# QUDONG.net
KiCad netlist of a schematic drawn in Altium Designer
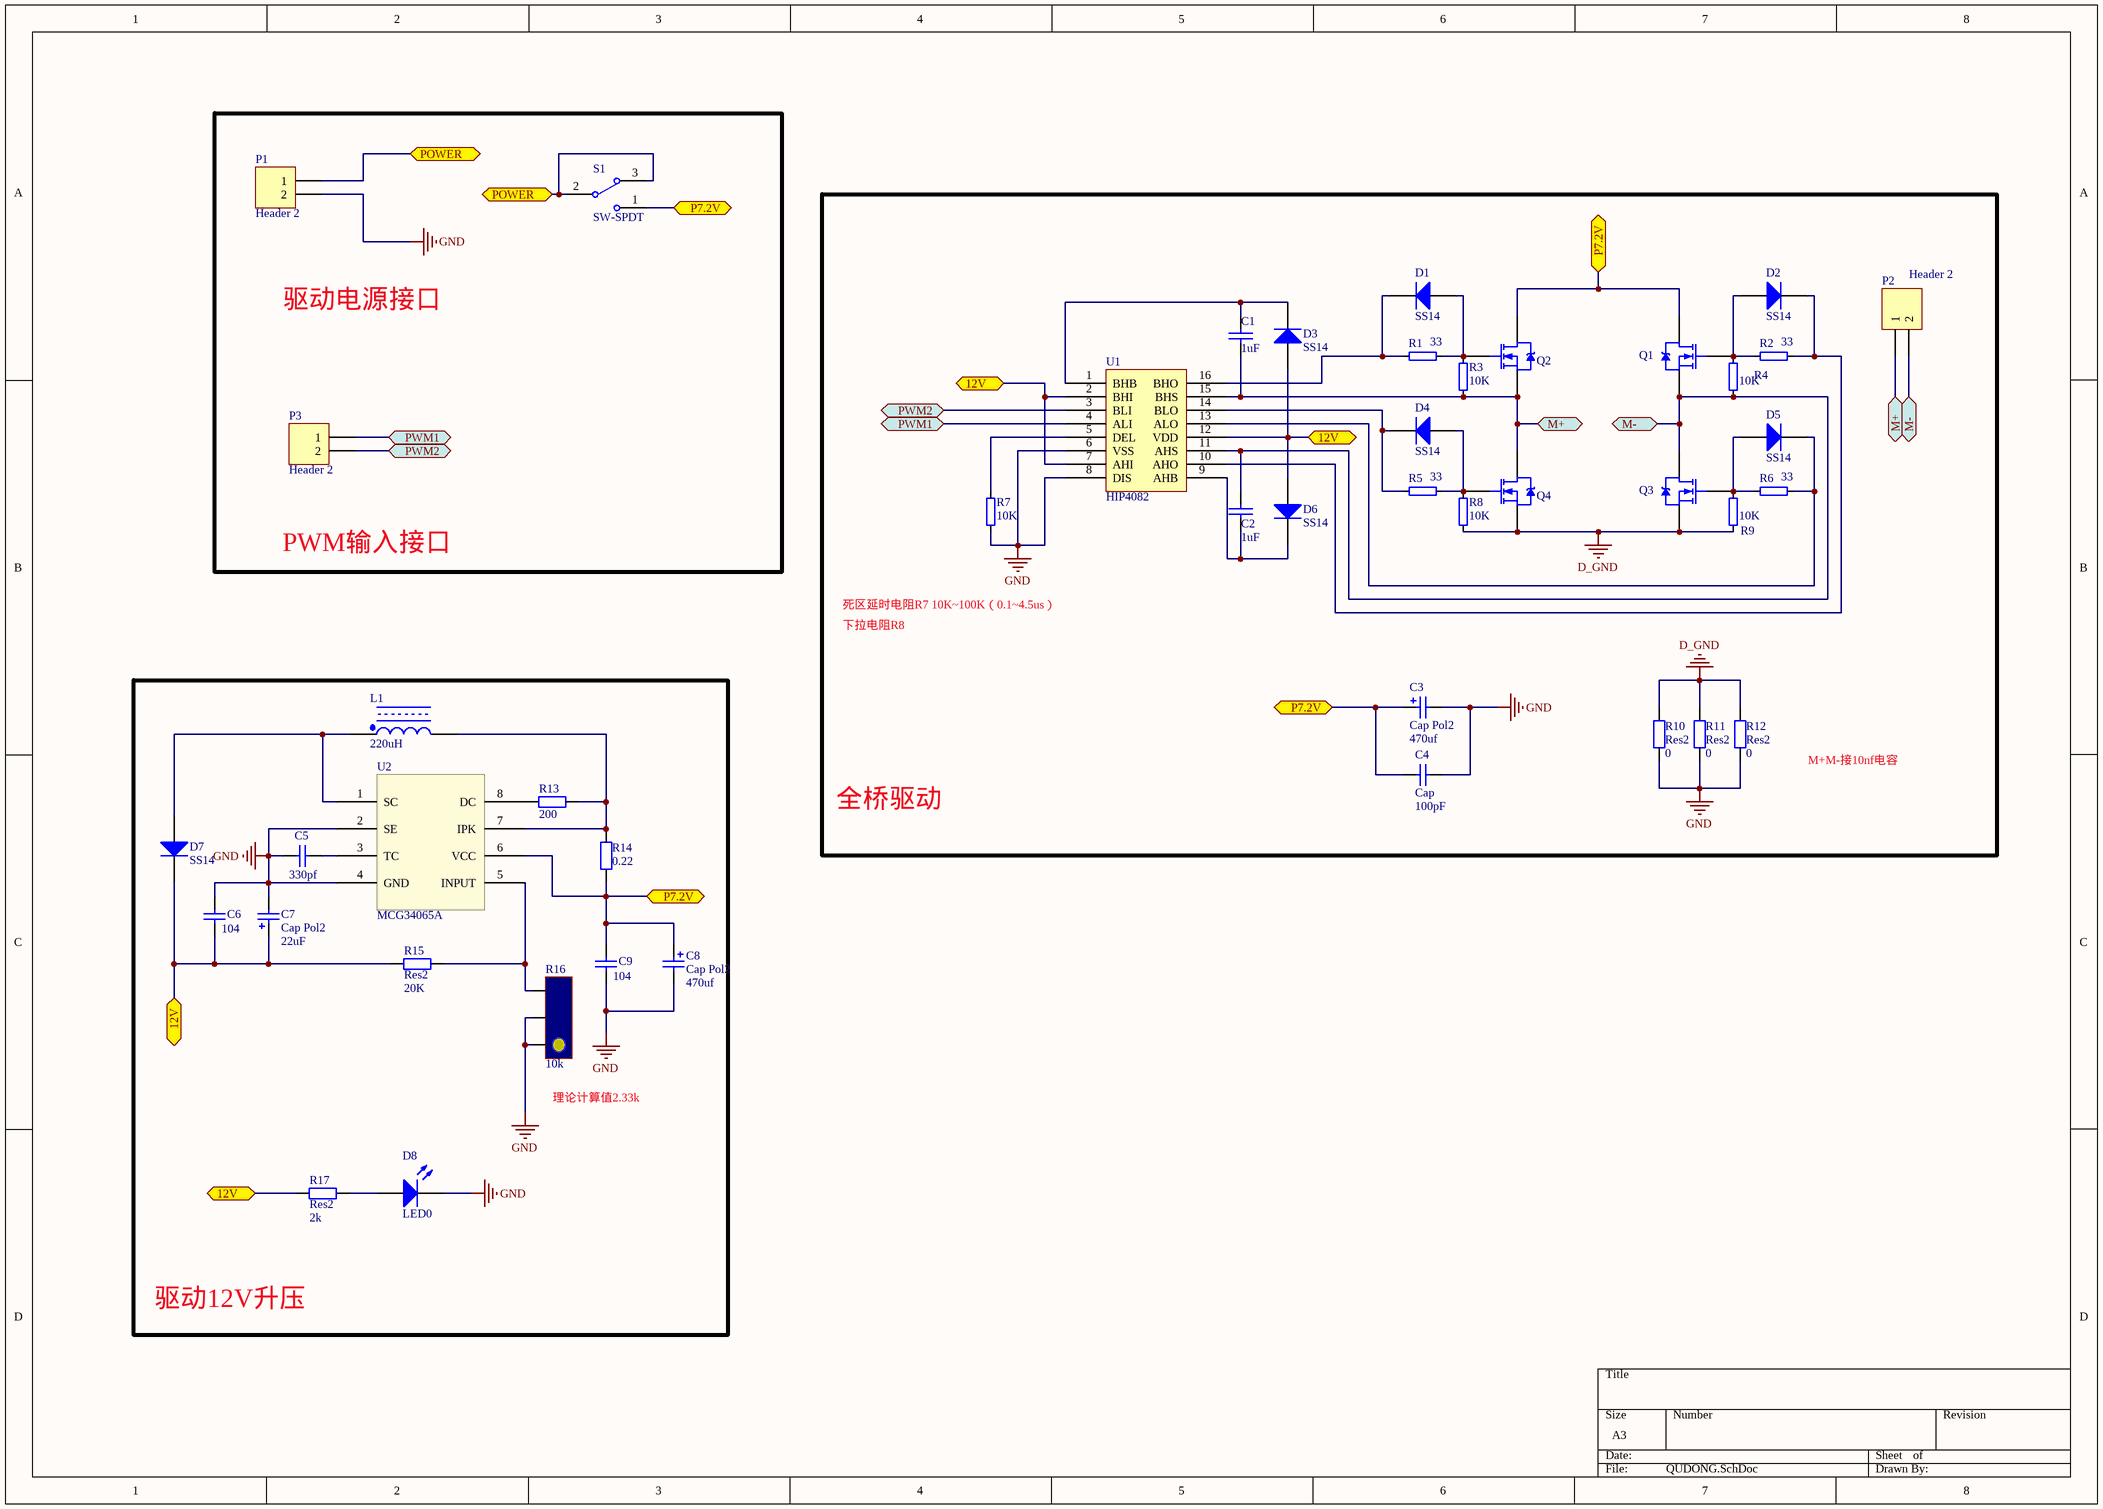
[diagram p0: QUDONG.SchDoc]

(export (version "E")
  (design (tool "Eeschema 10.0.6"))
  (components
    (comp (ref "C1")
      (value "1uF")
      (footprint "C-0805")
      (description "Capacitor")
      (libsource (lib "ZQ元件库") (part "CAP"))
    )
    (comp (ref "C2")
      (value "1uF")
      (footprint "C-0805")
      (description "Capacitor")
      (libsource (lib "ZQ元件库") (part "CAP"))
    )
    (comp (ref "C3")
      (value "Cap Pol2")
      (footprint "CAP-E1")
      (description "Polarized Capacitor (Axial)")
      (fields (field (name "ALTIUM_VALUE") "470uf") (field (name "PUBLISHER") "Altium Limited"))
      (libsource (lib "Miscellaneous Devices") (part "Cap Pol2"))
    )
    (comp (ref "C4")
      (value "Cap")
      (footprint "C-0805")
      (description "Capacitor")
      (fields (field (name "ALTIUM_VALUE") "100pF") (field (name "PUBLISHER") "Altium Limited"))
      (libsource (lib "Miscellaneous Devices") (part "Cap"))
    )
    (comp (ref "C5")
      (value "330pf")
      (footprint "C-0805")
      (description "Capacitor")
      (fields (field (name "Comment") "Cap") (field (name "PUBLISHER") "Altium Limited"))
      (libsource (lib "Miscellaneous Devices") (part "Cap"))
    )
    (comp (ref "C6")
      (value "104")
      (footprint "C-0805")
      (description "Capacitor")
      (fields (field (name "Comment") "Cap") (field (name "PUBLISHER") "Altium Limited"))
      (libsource (lib "Miscellaneous Devices") (part "Cap"))
    )
    (comp (ref "C7")
      (value "Cap Pol2")
      (footprint "1206")
      (description "Polarized Capacitor (Axial)")
      (fields (field (name "ALTIUM_VALUE") "22uF") (field (name "PUBLISHER") "Altium Limited"))
      (libsource (lib "Miscellaneous Devices") (part "Cap Pol2"))
    )
    (comp (ref "C8")
      (value "Cap Pol2")
      (footprint "CAP-E1")
      (description "Polarized Capacitor (Axial)")
      (fields (field (name "ALTIUM_VALUE") "470uf") (field (name "PUBLISHER") "Altium Limited"))
      (libsource (lib "Miscellaneous Devices") (part "Cap Pol2"))
    )
    (comp (ref "C9")
      (value "104")
      (footprint "C-0805")
      (description "Capacitor")
      (fields (field (name "Comment") "Cap") (field (name "PUBLISHER") "Altium Limited"))
      (libsource (lib "Miscellaneous Devices") (part "Cap"))
    )
    (comp (ref "D1")
      (value "SS14")
      (footprint "SOT-123")
      (description "High Conductance Fast Diode")
      (fields (field (name "PUBLISHER") "Altium Limited"))
      (libsource (lib "Miscellaneous Devices") (part "Diode 1N4148"))
    )
    (comp (ref "D2")
      (value "SS14")
      (footprint "SOT-123")
      (description "High Conductance Fast Diode")
      (fields (field (name "PUBLISHER") "Altium Limited"))
      (libsource (lib "Miscellaneous Devices") (part "Diode 1N4148"))
    )
    (comp (ref "D3")
      (value "SS14")
      (footprint "DO214AA")
      (description "High Conductance Fast Diode")
      (fields (field (name "PUBLISHER") "Altium Limited"))
      (libsource (lib "Miscellaneous Devices") (part "Diode 1N4148"))
    )
    (comp (ref "D4")
      (value "SS14")
      (footprint "SOT-123")
      (description "High Conductance Fast Diode")
      (fields (field (name "PUBLISHER") "Altium Limited"))
      (libsource (lib "Miscellaneous Devices") (part "Diode 1N4148"))
    )
    (comp (ref "D5")
      (value "SS14")
      (footprint "SOT-123")
      (description "High Conductance Fast Diode")
      (fields (field (name "PUBLISHER") "Altium Limited"))
      (libsource (lib "Miscellaneous Devices") (part "Diode 1N4148"))
    )
    (comp (ref "D6")
      (value "SS14")
      (footprint "DO214AA")
      (description "High Conductance Fast Diode")
      (fields (field (name "PUBLISHER") "Altium Limited"))
      (libsource (lib "Miscellaneous Devices") (part "Diode 1N4148"))
    )
    (comp (ref "D7")
      (value "SS14")
      (footprint "DO214AA")
      (description "Default Diode")
      (fields (field (name "PUBLISHER") "Altium Limited"))
      (libsource (lib "Miscellaneous Devices") (part "Diode"))
    )
    (comp (ref "D8")
      (value "LED0")
      (footprint "6-0805_N")
      (description "Typical INFRARED GaAs LED")
      (fields (field (name "PUBLISHER") "Altium Limited"))
      (libsource (lib "Miscellaneous Devices") (part "LED0"))
    )
    (comp (ref "L1")
      (value "220uH")
      (footprint "L-SMD-7")
      (description "磁芯电感")
      (libsource (lib "电阻-电容-电感") (part "L-D-SMD"))
    )
    (comp (ref "P1")
      (value "Header 2")
      (footprint "T型插头(公)")
      (description "Header, 2-Pin")
      (fields (field (name "PUBLISHER") "Altium Limited"))
      (libsource (lib "Miscellaneous Connectors") (part "Header 2"))
    )
    (comp (ref "P2")
      (value "Header 2")
      (footprint "接线柱")
      (description "Header, 2-Pin")
      (fields (field (name "PUBLISHER") "Altium Limited"))
      (libsource (lib "") (part "Header 2_1"))
    )
    (comp (ref "P3")
      (value "Header 2")
      (footprint "2PIN-弯")
      (description "Header, 2-Pin")
      (fields (field (name "PUBLISHER") "Altium Limited"))
      (libsource (lib "Miscellaneous Connectors") (part "Header 2"))
    )
    (comp (ref "Q1") (value "IRF3205") (footprint "TO-252AA_M") (libsource (lib "常用封装") (part "IRLR7843")))
    (comp (ref "Q2") (value "IRF3205") (footprint "TO-252AA_M") (libsource (lib "常用封装") (part "IRLR7843")))
    (comp (ref "Q3") (value "IRF3205") (footprint "TO-252AA_M") (libsource (lib "常用封装") (part "IRLR7843")))
    (comp (ref "Q4") (value "IRF3205") (footprint "TO-252AA_M") (libsource (lib "常用封装") (part "IRLR7843")))
    (comp (ref "R1") (value "33") (footprint "0805") (libsource (lib "ZQ元件库") (part "RES")))
    (comp (ref "R2") (value "33") (footprint "0805") (libsource (lib "ZQ元件库") (part "RES")))
    (comp (ref "R3") (value "10K") (footprint "0805") (libsource (lib "ZQ元件库") (part "RES")))
    (comp (ref "R4") (value "10K") (footprint "0805") (libsource (lib "ZQ元件库") (part "RES")))
    (comp (ref "R5") (value "33") (footprint "0805") (libsource (lib "ZQ元件库") (part "RES")))
    (comp (ref "R6") (value "33") (footprint "0805") (libsource (lib "ZQ元件库") (part "RES")))
    (comp (ref "R7") (value "10K") (footprint "0805") (libsource (lib "ZQ元件库") (part "RES")))
    (comp (ref "R8") (value "10K") (footprint "0805") (libsource (lib "ZQ元件库") (part "RES")))
    (comp (ref "R9") (value "10K") (footprint "0805") (libsource (lib "ZQ元件库") (part "RES")))
    (comp (ref "R10")
      (value "Res2")
      (footprint "0805")
      (description "Resistor")
      (fields (field (name "ALTIUM_VALUE") "0") (field (name "PUBLISHER") "Altium Limited"))
      (libsource (lib "Miscellaneous Devices") (part "Res2"))
    )
    (comp (ref "R11")
      (value "Res2")
      (footprint "0805")
      (description "Resistor")
      (fields (field (name "ALTIUM_VALUE") "0") (field (name "PUBLISHER") "Altium Limited"))
      (libsource (lib "Miscellaneous Devices") (part "Res2"))
    )
    (comp (ref "R12")
      (value "Res2")
      (footprint "0805")
      (description "Resistor")
      (fields (field (name "ALTIUM_VALUE") "0") (field (name "PUBLISHER") "Altium Limited"))
      (libsource (lib "Miscellaneous Devices") (part "Res2"))
    )
    (comp (ref "R13")
      (value "200")
      (footprint "0805")
      (description "Resistor")
      (fields (field (name "Comment") "Res2") (field (name "PUBLISHER") "Altium Limited"))
      (libsource (lib "") (part "Res2_2"))
    )
    (comp (ref "R14")
      (value "0.22")
      (footprint "0805")
      (description "Resistor")
      (fields (field (name "Comment") "Res2") (field (name "PUBLISHER") "Altium Limited"))
      (libsource (lib "") (part "Res2_3"))
    )
    (comp (ref "R15")
      (value "Res2")
      (footprint "0805")
      (description "Resistor")
      (fields (field (name "ALTIUM_VALUE") "20K") (field (name "PUBLISHER") "Altium Limited"))
      (libsource (lib "") (part "Res2_2"))
    )
    (comp (ref "R16")
      (value "10k")
      (footprint "T-3224w")
      (fields (field (name "Comment") "RES-ADJ"))
      (libsource (lib "常用封装") (part "RES-ADJ"))
    )
    (comp (ref "R17")
      (value "Res2")
      (footprint "0805")
      (description "Resistor")
      (fields (field (name "ALTIUM_VALUE") "2k") (field (name "PUBLISHER") "Altium Limited"))
      (libsource (lib "") (part "Res2_1"))
    )
    (comp (ref "S1")
      (value "SW-SPDT")
      (footprint "SWITCH_B")
      (description "SPDT Subminiature Toggle Switch, Right Angle Mounting, Vertical Actuation")
      (fields (field (name "PUBLISHER") "Altium Limited"))
      (libsource (lib "Miscellaneous Devices") (part "SW-SPDT"))
    )
    (comp (ref "U1") (value "HIP4082") (footprint "SO-16N") (libsource (lib "SCH_IC") (part "HIP4082")))
    (comp (ref "U2") (value "MCG34065A") (footprint "SO-8") (libsource (lib "常用封装") (part "MCG34065A")))
  )
  (nets
    (net (code "1") (name "/12V") (class "Default")
      (node (ref "C6") (pin "2") (pinfunction "2_2") (pintype "passive"))
      (node (ref "C7") (pin "1") (pinfunction "1_1") (pintype "passive"))
      (node (ref "D3") (pin "1") (pinfunction "A_1") (pintype "passive"))
      (node (ref "D6") (pin "1") (pinfunction "A_1") (pintype "passive"))
      (node (ref "D7") (pin "2") (pinfunction "K_2") (pintype "passive"))
      (node (ref "R15") (pin "2") (pinfunction "2_2") (pintype "passive"))
      (node (ref "R17") (pin "1") (pinfunction "1_1") (pintype "passive"))
      (node (ref "U1") (pin "12") (pinfunction "VDD_12") (pintype "passive"))
      (node (ref "U1") (pin "2") (pinfunction "BHI_2") (pintype "passive"))
      (node (ref "U1") (pin "7") (pinfunction "AHI_7") (pintype "passive"))
    )
    (net (code "2") (name "/M+") (class "Default")
      (node (ref "C1") (pin "1") (pinfunction "1_1") (pintype "passive"))
      (node (ref "P2") (pin "1") (pinfunction "1_1") (pintype "passive"))
      (node (ref "Q2") (pin "3") (pinfunction "S_3") (pintype "passive"))
      (node (ref "Q4") (pin "4") (pinfunction "D_4") (pintype "passive"))
      (node (ref "R3") (pin "1") (pinfunction "1_1") (pintype "passive"))
      (node (ref "U1") (pin "15") (pinfunction "BHS_15") (pintype "passive"))
    )
    (net (code "3") (name "/M-") (class "Default")
      (node (ref "C2") (pin "2") (pinfunction "2_2") (pintype "passive"))
      (node (ref "P2") (pin "2") (pinfunction "2_2") (pintype "passive"))
      (node (ref "Q1") (pin "3") (pinfunction "S_3") (pintype "passive"))
      (node (ref "Q3") (pin "4") (pinfunction "D_4") (pintype "passive"))
      (node (ref "R4") (pin "1") (pinfunction "1_1") (pintype "passive"))
      (node (ref "U1") (pin "11") (pinfunction "AHS_11") (pintype "passive"))
    )
    (net (code "4") (name "/P7.2V") (class "Default")
      (node (ref "C3") (pin "1") (pinfunction "1_1") (pintype "passive"))
      (node (ref "C4") (pin "2") (pinfunction "2_2") (pintype "passive"))
      (node (ref "C8") (pin "1") (pinfunction "1_1") (pintype "passive"))
      (node (ref "C9") (pin "1") (pinfunction "1_1") (pintype "passive"))
      (node (ref "Q1") (pin "4") (pinfunction "D_4") (pintype "passive"))
      (node (ref "Q2") (pin "4") (pinfunction "D_4") (pintype "passive"))
      (node (ref "R14") (pin "2") (pinfunction "2_2") (pintype "passive"))
      (node (ref "S1") (pin "1") (pinfunction "1_1") (pintype "passive"))
      (node (ref "U2") (pin "6") (pinfunction "VCC_6") (pintype "power_in"))
    )
    (net (code "5") (name "/POWER") (class "Default")
      (node (ref "P1") (pin "1") (pinfunction "1_1") (pintype "passive"))
      (node (ref "S1") (pin "2") (pinfunction "2_2") (pintype "passive"))
      (node (ref "S1") (pin "3") (pinfunction "3_3") (pintype "passive"))
    )
    (net (code "6") (name "/PWM1") (class "Default")
      (node (ref "P3") (pin "1") (pinfunction "1_1") (pintype "passive"))
      (node (ref "U1") (pin "4") (pinfunction "ALI_4") (pintype "passive"))
    )
    (net (code "7") (name "/PWM2") (class "Default")
      (node (ref "P3") (pin "2") (pinfunction "2_2") (pintype "passive"))
      (node (ref "U1") (pin "3") (pinfunction "BLI_3") (pintype "passive"))
    )
    (net (code "8") (name "D_GND") (class "Default")
      (node (ref "Q3") (pin "3") (pinfunction "S_3") (pintype "passive"))
      (node (ref "Q4") (pin "3") (pinfunction "S_3") (pintype "passive"))
      (node (ref "R10") (pin "2") (pinfunction "2_2") (pintype "passive"))
      (node (ref "R11") (pin "2") (pinfunction "2_2") (pintype "passive"))
      (node (ref "R12") (pin "2") (pinfunction "2_2") (pintype "passive"))
      (node (ref "R8") (pin "1") (pinfunction "1_1") (pintype "passive"))
      (node (ref "R9") (pin "1") (pinfunction "1_1") (pintype "passive"))
    )
    (net (code "9") (name "GND") (class "Default")
      (node (ref "C3") (pin "2") (pinfunction "2_2") (pintype "passive"))
      (node (ref "C4") (pin "1") (pinfunction "1_1") (pintype "passive"))
      (node (ref "C5") (pin "2") (pinfunction "2_2") (pintype "passive"))
      (node (ref "C6") (pin "1") (pinfunction "1_1") (pintype "passive"))
      (node (ref "C7") (pin "2") (pinfunction "2_2") (pintype "passive"))
      (node (ref "C8") (pin "2") (pinfunction "2_2") (pintype "passive"))
      (node (ref "C9") (pin "2") (pinfunction "2_2") (pintype "passive"))
      (node (ref "D8") (pin "2") (pinfunction "K_2") (pintype "passive"))
      (node (ref "P1") (pin "2") (pinfunction "2_2") (pintype "passive"))
      (node (ref "R10") (pin "1") (pinfunction "1_1") (pintype "passive"))
      (node (ref "R11") (pin "1") (pinfunction "1_1") (pintype "passive"))
      (node (ref "R12") (pin "1") (pinfunction "1_1") (pintype "passive"))
      (node (ref "R16") (pin "2") (pinfunction "2_2") (pintype "passive"))
      (node (ref "R16") (pin "3") (pinfunction "3_3") (pintype "passive"))
      (node (ref "R7") (pin "2") (pinfunction "2_2") (pintype "passive"))
      (node (ref "U1") (pin "6") (pinfunction "VSS_6") (pintype "passive"))
      (node (ref "U1") (pin "8") (pinfunction "DIS_8") (pintype "passive"))
      (node (ref "U2") (pin "2") (pinfunction "SE_2") (pintype "passive"))
      (node (ref "U2") (pin "4") (pinfunction "GND_4") (pintype "power_in"))
    )
    (net (code "10") (name "Net-(D1-A)") (class "Default")
      (node (ref "D1") (pin "1") (pinfunction "A_1") (pintype "passive"))
      (node (ref "Q2") (pin "1") (pinfunction "G_1") (pintype "passive"))
      (node (ref "R1") (pin "2") (pinfunction "2_2") (pintype "passive"))
      (node (ref "R3") (pin "2") (pinfunction "2_2") (pintype "passive"))
    )
    (net (code "11") (name "Net-(D1-K)") (class "Default")
      (node (ref "D1") (pin "2") (pinfunction "K_2") (pintype "passive"))
      (node (ref "R1") (pin "1") (pinfunction "1_1") (pintype "passive"))
      (node (ref "U1") (pin "16") (pinfunction "BHO_16") (pintype "passive"))
    )
    (net (code "12") (name "Net-(D2-A)") (class "Default")
      (node (ref "D2") (pin "1") (pinfunction "A_1") (pintype "passive"))
      (node (ref "Q1") (pin "1") (pinfunction "G_1") (pintype "passive"))
      (node (ref "R2") (pin "1") (pinfunction "1_1") (pintype "passive"))
      (node (ref "R4") (pin "2") (pinfunction "2_2") (pintype "passive"))
    )
    (net (code "13") (name "Net-(D2-K)") (class "Default")
      (node (ref "D2") (pin "2") (pinfunction "K_2") (pintype "passive"))
      (node (ref "R2") (pin "2") (pinfunction "2_2") (pintype "passive"))
      (node (ref "U1") (pin "10") (pinfunction "AHO_10") (pintype "passive"))
    )
    (net (code "14") (name "Net-(D3-K)") (class "Default")
      (node (ref "C1") (pin "2") (pinfunction "2_2") (pintype "passive"))
      (node (ref "D3") (pin "2") (pinfunction "K_2") (pintype "passive"))
      (node (ref "U1") (pin "1") (pinfunction "BHB_1") (pintype "passive"))
    )
    (net (code "15") (name "Net-(D4-A)") (class "Default")
      (node (ref "D4") (pin "1") (pinfunction "A_1") (pintype "passive"))
      (node (ref "Q4") (pin "1") (pinfunction "G_1") (pintype "passive"))
      (node (ref "R5") (pin "2") (pinfunction "2_2") (pintype "passive"))
      (node (ref "R8") (pin "2") (pinfunction "2_2") (pintype "passive"))
    )
    (net (code "16") (name "Net-(D4-K)") (class "Default")
      (node (ref "D4") (pin "2") (pinfunction "K_2") (pintype "passive"))
      (node (ref "R5") (pin "1") (pinfunction "1_1") (pintype "passive"))
      (node (ref "U1") (pin "14") (pinfunction "BLO_14") (pintype "passive"))
    )
    (net (code "17") (name "Net-(D5-A)") (class "Default")
      (node (ref "D5") (pin "1") (pinfunction "A_1") (pintype "passive"))
      (node (ref "Q3") (pin "1") (pinfunction "G_1") (pintype "passive"))
      (node (ref "R6") (pin "1") (pinfunction "1_1") (pintype "passive"))
      (node (ref "R9") (pin "2") (pinfunction "2_2") (pintype "passive"))
    )
    (net (code "18") (name "Net-(D5-K)") (class "Default")
      (node (ref "D5") (pin "2") (pinfunction "K_2") (pintype "passive"))
      (node (ref "R6") (pin "2") (pinfunction "2_2") (pintype "passive"))
      (node (ref "U1") (pin "13") (pinfunction "ALO_13") (pintype "passive"))
    )
    (net (code "19") (name "Net-(D6-K)") (class "Default")
      (node (ref "C2") (pin "1") (pinfunction "1_1") (pintype "passive"))
      (node (ref "D6") (pin "2") (pinfunction "K_2") (pintype "passive"))
      (node (ref "U1") (pin "9") (pinfunction "AHB_9") (pintype "passive"))
    )
    (net (code "20") (name "Net-(D7-A)") (class "Default")
      (node (ref "D7") (pin "1") (pinfunction "A_1") (pintype "passive"))
      (node (ref "L1") (pin "1") (pinfunction "1_1") (pintype "passive"))
      (node (ref "U2") (pin "1") (pinfunction "SC_1") (pintype "passive"))
    )
    (net (code "21") (name "Net-(D8-A)") (class "Default")
      (node (ref "D8") (pin "1") (pinfunction "A_1") (pintype "passive"))
      (node (ref "R17") (pin "2") (pinfunction "2_2") (pintype "passive"))
    )
    (net (code "22") (name "Net-(U1-DEL)") (class "Default")
      (node (ref "R7") (pin "1") (pinfunction "1_1") (pintype "passive"))
      (node (ref "U1") (pin "5") (pinfunction "DEL_5") (pintype "passive"))
    )
    (net (code "23") (name "Net-(U2-DC)") (class "Default")
      (node (ref "R13") (pin "2") (pinfunction "2_2") (pintype "passive"))
      (node (ref "U2") (pin "8") (pinfunction "DC_8") (pintype "passive"))
    )
    (net (code "24") (name "Net-(U2-INPUT)") (class "Default")
      (node (ref "R15") (pin "1") (pinfunction "1_1") (pintype "passive"))
      (node (ref "R16") (pin "1") (pinfunction "1_1") (pintype "passive"))
      (node (ref "U2") (pin "5") (pinfunction "INPUT_5") (pintype "passive"))
    )
    (net (code "25") (name "Net-(U2-IPK)") (class "Default")
      (node (ref "L1") (pin "2") (pinfunction "2_2") (pintype "passive"))
      (node (ref "R13") (pin "1") (pinfunction "1_1") (pintype "passive"))
      (node (ref "R14") (pin "1") (pinfunction "1_1") (pintype "passive"))
      (node (ref "U2") (pin "7") (pinfunction "IPK_7") (pintype "passive"))
    )
    (net (code "26") (name "Net-(U2-TC)") (class "Default")
      (node (ref "C5") (pin "1") (pinfunction "1_1") (pintype "passive"))
      (node (ref "U2") (pin "3") (pinfunction "TC_3") (pintype "passive"))
    )
  )
)
